# PWR_0V9_20A.net
KiCad netlist of a schematic drawn in Altium Designer
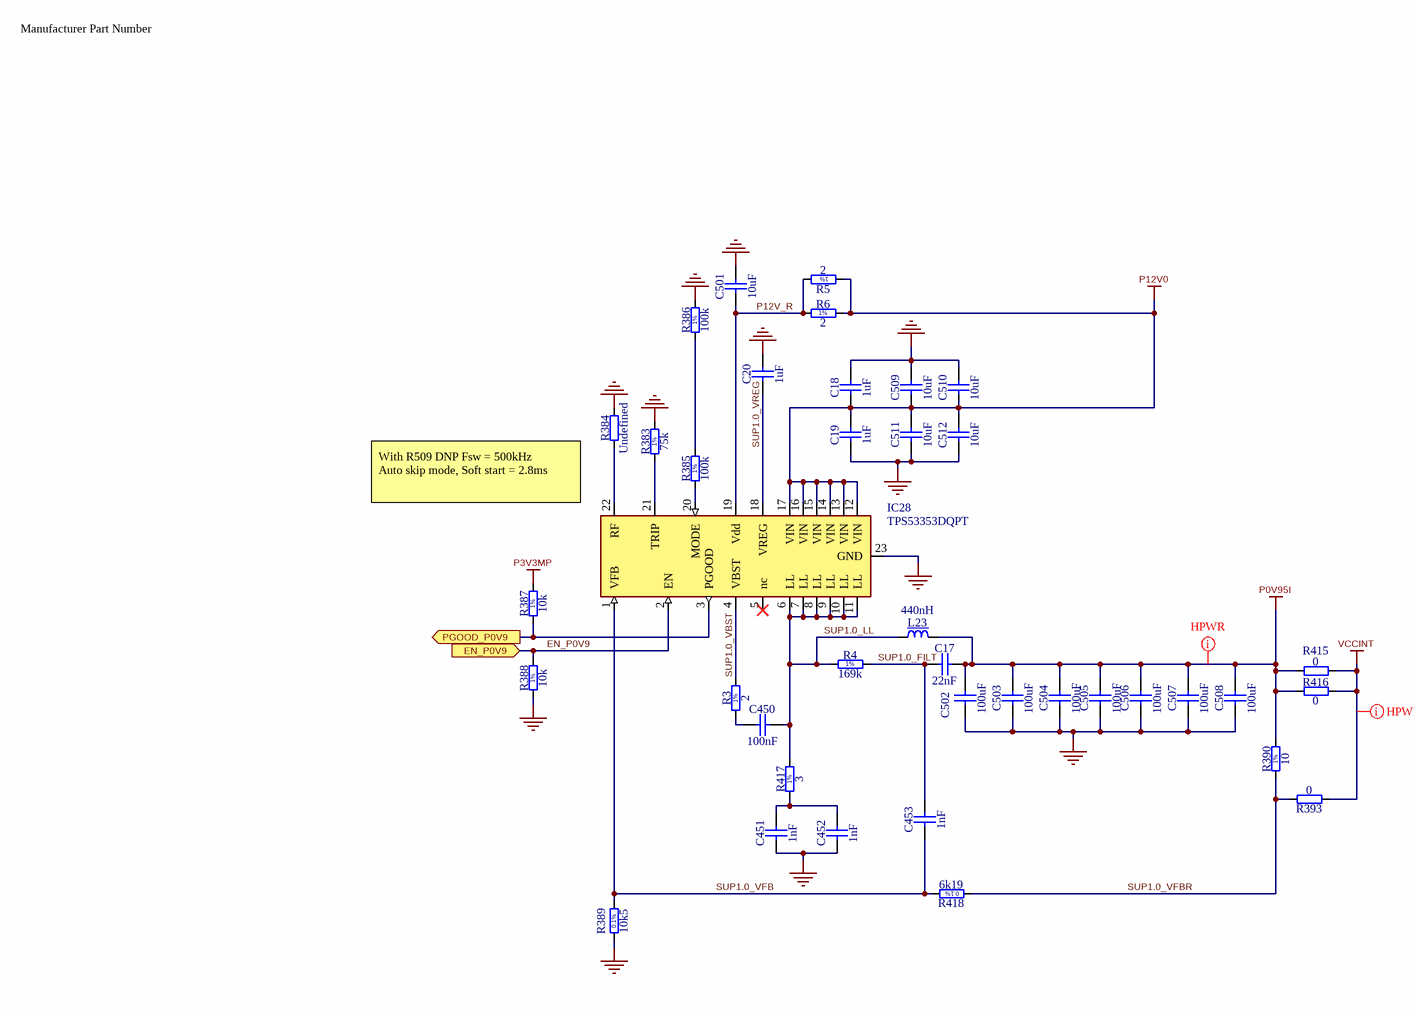
[diagram p0: PWR_0V9_20A.SchDoc]

(export (version "E")
  (design (tool "Eeschema 10.0.6"))
  (components
    (comp (ref "C17")
      (value "22nF")
      (footprint "CAPC1608X87N")
      (description "Non-polarised capacitor")
      (fields
        (field (name "MANUFACTURER PART NUMBER") "CC0603_22NF_50V_10%_X7R")
        (field (name "MANUFACTURER") "GENERIC")
        (field (name "AUTHOR") "CERN DEM JLC")
      )
      (libsource (lib "Capacitors") (part "Capacitor - non polarized"))
    )
    (comp (ref "C18")
      (value "1uF")
      (footprint "CAPC1608X87N")
      (description "Non-polarised capacitor")
      (fields
        (field (name "MANUFACTURER PART NUMBER") "CC0603_1UF_25V_10%_X7R")
        (field (name "MANUFACTURER") "GENERIC")
        (field (name "AUTHOR") "CERN DEM JLC")
      )
      (libsource (lib "Capacitors") (part "Capacitor - non polarized"))
    )
    (comp (ref "C19")
      (value "1uF")
      (footprint "CAPC1608X87N")
      (description "Non-polarised capacitor")
      (fields
        (field (name "MANUFACTURER PART NUMBER") "CC0603_1UF_25V_10%_X7R")
        (field (name "MANUFACTURER") "GENERIC")
        (field (name "AUTHOR") "CERN DEM JLC")
      )
      (libsource (lib "Capacitors") (part "Capacitor - non polarized"))
    )
    (comp (ref "C20")
      (value "1uF")
      (footprint "CAPC1608X87N")
      (description "Non-polarised capacitor")
      (fields
        (field (name "MANUFACTURER PART NUMBER") "CC0603_1UF_25V_10%_X7R")
        (field (name "MANUFACTURER") "GENERIC")
        (field (name "AUTHOR") "CERN DEM JLC")
      )
      (libsource (lib "Capacitors") (part "Capacitor - non polarized"))
    )
    (comp (ref "C450")
      (value "100nF")
      (footprint "CAPC1005X55N")
      (description "Non-polarised capacitor")
      (fields
        (field (name "MANUFACTURER PART NUMBER") "CC0402_100NF_16V_10%_X5R")
        (field (name "MANUFACTURER") "GENERIC")
        (field (name "AUTHOR") "CERN DEM JLC")
      )
      (libsource (lib "Capacitors") (part "Capacitor - non polarized"))
    )
    (comp (ref "C451")
      (value "1nF")
      (footprint "CAPC1005X55N")
      (description "Non-polarised capacitor")
      (fields
        (field (name "MANUFACTURER PART NUMBER") "CC0402_1NF_50V_10%_X7R")
        (field (name "MANUFACTURER") "GENERIC")
        (field (name "AUTHOR") "CERN DEM JLC")
      )
      (libsource (lib "Capacitors") (part "Capacitor - non polarized"))
    )
    (comp (ref "C452")
      (value "1nF")
      (footprint "CAPC1005X55N")
      (description "Non-polarised capacitor")
      (fields
        (field (name "MANUFACTURER PART NUMBER") "CC0402_1NF_50V_10%_X7R")
        (field (name "MANUFACTURER") "GENERIC")
        (field (name "AUTHOR") "CERN DEM JLC")
      )
      (libsource (lib "Capacitors") (part "Capacitor - non polarized"))
    )
    (comp (ref "C453")
      (value "1nF")
      (footprint "CAPC1005X55N")
      (description "Non-polarised capacitor")
      (fields
        (field (name "MANUFACTURER PART NUMBER") "CC0402_1NF_50V_10%_X7R")
        (field (name "MANUFACTURER") "GENERIC")
        (field (name "AUTHOR") "CERN DEM JLC")
      )
      (libsource (lib "Capacitors") (part "Capacitor - non polarized"))
    )
    (comp (ref "C501")
      (value "10uF")
      (footprint "CAPC3216X180N")
      (description "Non-polarised capacitor")
      (fields
        (field (name "MANUFACTURER PART NUMBER") "CC1206_10uF_25V_10%_X7R")
        (field (name "MANUFACTURER") "GENERIC")
        (field (name "AUTHOR") "CERN DEM JLC")
      )
      (libsource (lib "Capacitors") (part "Capacitor - non polarized"))
    )
    (comp (ref "C502")
      (value "100uF")
      (footprint "CAPC3216X180N")
      (description "Non-polarised capacitor")
      (fields
        (field (name "MANUFACTURER PART NUMBER") "CC1206_100UF_6.3V_20%_X5R")
        (field (name "MANUFACTURER") "GENERIC")
        (field (name "AUTHOR") "CERN DEM JLC")
      )
      (libsource (lib "Capacitors") (part "Capacitor - non polarized"))
    )
    (comp (ref "C503")
      (value "100uF")
      (footprint "CAPC3216X180N")
      (description "Non-polarised capacitor")
      (fields
        (field (name "MANUFACTURER PART NUMBER") "CC1206_100UF_6.3V_20%_X5R")
        (field (name "MANUFACTURER") "GENERIC")
        (field (name "AUTHOR") "CERN DEM JLC")
      )
      (libsource (lib "Capacitors") (part "Capacitor - non polarized"))
    )
    (comp (ref "C504")
      (value "100uF")
      (footprint "CAPC3216X180N")
      (description "Non-polarised capacitor")
      (fields
        (field (name "MANUFACTURER PART NUMBER") "CC1206_100UF_6.3V_20%_X5R")
        (field (name "MANUFACTURER") "GENERIC")
        (field (name "AUTHOR") "CERN DEM JLC")
      )
      (libsource (lib "Capacitors") (part "Capacitor - non polarized"))
    )
    (comp (ref "C505")
      (value "100uF")
      (footprint "CAPC3216X180N")
      (description "Non-polarised capacitor")
      (fields
        (field (name "MANUFACTURER PART NUMBER") "CC1206_100UF_6.3V_20%_X5R")
        (field (name "MANUFACTURER") "GENERIC")
        (field (name "AUTHOR") "CERN DEM JLC")
      )
      (libsource (lib "Capacitors") (part "Capacitor - non polarized"))
    )
    (comp (ref "C506")
      (value "100uF")
      (footprint "CAPC3216X180N")
      (description "Non-polarised capacitor")
      (fields
        (field (name "MANUFACTURER PART NUMBER") "CC1206_100UF_6.3V_20%_X5R")
        (field (name "MANUFACTURER") "GENERIC")
        (field (name "AUTHOR") "CERN DEM JLC")
      )
      (libsource (lib "Capacitors") (part "Capacitor - non polarized"))
    )
    (comp (ref "C507")
      (value "100uF")
      (footprint "CAPC3216X180N")
      (description "Non-polarised capacitor")
      (fields
        (field (name "MANUFACTURER PART NUMBER") "CC1206_100UF_6.3V_20%_X5R")
        (field (name "MANUFACTURER") "GENERIC")
        (field (name "AUTHOR") "CERN DEM JLC")
      )
      (libsource (lib "Capacitors") (part "Capacitor - non polarized"))
    )
    (comp (ref "C508")
      (value "100uF")
      (footprint "CAPC3216X180N")
      (description "Non-polarised capacitor")
      (fields
        (field (name "MANUFACTURER PART NUMBER") "CC1206_100UF_6.3V_20%_X5R")
        (field (name "MANUFACTURER") "GENERIC")
        (field (name "AUTHOR") "CERN DEM JLC")
      )
      (libsource (lib "Capacitors") (part "Capacitor - non polarized"))
    )
    (comp (ref "C509")
      (value "10uF")
      (footprint "CAPC3216X180N")
      (description "Non-polarised capacitor")
      (fields
        (field (name "MANUFACTURER PART NUMBER") "CC1206_10uF_25V_10%_X7R")
        (field (name "MANUFACTURER") "GENERIC")
        (field (name "AUTHOR") "CERN DEM JLC")
      )
      (libsource (lib "Capacitors") (part "Capacitor - non polarized"))
    )
    (comp (ref "C510")
      (value "10uF")
      (footprint "CAPC3216X180N")
      (description "Non-polarised capacitor")
      (fields
        (field (name "MANUFACTURER PART NUMBER") "CC1206_10uF_25V_10%_X7R")
        (field (name "MANUFACTURER") "GENERIC")
        (field (name "AUTHOR") "CERN DEM JLC")
      )
      (libsource (lib "Capacitors") (part "Capacitor - non polarized"))
    )
    (comp (ref "C511")
      (value "10uF")
      (footprint "CAPC3216X180N")
      (description "Non-polarised capacitor")
      (fields
        (field (name "MANUFACTURER PART NUMBER") "CC1206_10uF_25V_10%_X7R")
        (field (name "MANUFACTURER") "GENERIC")
        (field (name "AUTHOR") "CERN DEM JLC")
      )
      (libsource (lib "Capacitors") (part "Capacitor - non polarized"))
    )
    (comp (ref "C512")
      (value "10uF")
      (footprint "CAPC3216X180N")
      (description "Non-polarised capacitor")
      (fields
        (field (name "MANUFACTURER PART NUMBER") "CC1206_10uF_25V_10%_X7R")
        (field (name "MANUFACTURER") "GENERIC")
        (field (name "AUTHOR") "CERN DEM JLC")
      )
      (libsource (lib "Capacitors") (part "Capacitor - non polarized"))
    )
    (comp (ref "IC28")
      (value "TPS53353DQPT")
      (footprint "LCCS50P600X500X150-22N")
      (description "High-Efficiency 20-A Synchronous Buck Converter with Eco-mode™")
      (libsource (lib "LIBRARY_SCH") (part "PM_TPS53353"))
    )
    (comp (ref "L23")
      (value "440nH")
      (footprint "IND_PULSE_PA0513")
      (description "Inductor With Core")
      (fields
        (field (name "MANUFACTURER PART NUMBER") "PA0513.441NLT")
        (field (name "MANUFACTURER") "PULSE ELECTRONICS")
        (field (name "AUTHOR") "CERN DEM JLC")
      )
      (libsource (lib "Inductors & Transformers") (part "Inductor With Magnetic core"))
    )
    (comp (ref "R3")
      (value "2")
      (footprint "RESC1608X55N")
      (description "Resistor - 1%")
      (fields
        (field (name "MANUFACTURER PART NUMBER") "R0603_2R_1%_0.1W_200PPM")
        (field (name "MANUFACTURER") "GENERIC")
        (field (name "AUTHOR") "CERN DEM JLC")
      )
      (libsource (lib "Resistors") (part "Resistor - 1%"))
    )
    (comp (ref "R4")
      (value "169k")
      (footprint "RESC1608X55N")
      (description "Resistor - 1%")
      (fields
        (field (name "MANUFACTURER PART NUMBER") "R0603_169K_1%_0.1W_100PPM")
        (field (name "MANUFACTURER") "GENERIC")
        (field (name "AUTHOR") "CERN DEM JLC")
      )
      (libsource (lib "Resistors") (part "Resistor - 1%"))
    )
    (comp (ref "R5")
      (value "2")
      (footprint "RESC1608X55N")
      (description "Resistor - 1%")
      (fields
        (field (name "MANUFACTURER PART NUMBER") "R0603_2R_1%_0.1W_200PPM")
        (field (name "MANUFACTURER") "GENERIC")
        (field (name "AUTHOR") "CERN DEM JLC")
      )
      (libsource (lib "Resistors") (part "Resistor - 1%"))
    )
    (comp (ref "R6")
      (value "2")
      (footprint "RESC1608X55N")
      (description "Resistor - 1%")
      (fields
        (field (name "MANUFACTURER PART NUMBER") "R0603_2R_1%_0.1W_200PPM")
        (field (name "MANUFACTURER") "GENERIC")
        (field (name "AUTHOR") "CERN DEM JLC")
      )
      (libsource (lib "Resistors") (part "Resistor - 1%"))
    )
    (comp (ref "R383")
      (value "75k")
      (footprint "RESC1005X40N")
      (description "Resistor - 1%")
      (fields
        (field (name "MANUFACTURER PART NUMBER") "R0402_75K_1%_0.0625W_100PPM")
        (field (name "MANUFACTURER") "GENERIC")
        (field (name "AUTHOR") "CERN DEM JLC")
      )
      (libsource (lib "Resistors") (part "Resistor - 1%"))
    )
    (comp (ref "R384")
      (value "Undefined")
      (footprint "RESC1005X40N")
      (description "Resistor")
      (fields
        (field (name "MANUFACTURER PART NUMBER") "R0402_NO-VALUE")
        (field (name "AUTHOR") "CERN DEM JLC")
      )
      (libsource (lib "Resistors") (part "Resistor"))
    )
    (comp (ref "R385")
      (value "100k")
      (footprint "RESC1005X40N")
      (description "Resistor - 1%")
      (fields
        (field (name "MANUFACTURER PART NUMBER") "R0402_100K_1%_0.0625W_100PPM")
        (field (name "MANUFACTURER") "GENERIC")
        (field (name "AUTHOR") "CERN DEM JLC")
      )
      (libsource (lib "Resistors") (part "Resistor - 1%"))
    )
    (comp (ref "R386")
      (value "100k")
      (footprint "RESC1005X40N")
      (description "Resistor - 1%")
      (fields
        (field (name "MANUFACTURER PART NUMBER") "R0402_100K_1%_0.0625W_100PPM")
        (field (name "MANUFACTURER") "GENERIC")
        (field (name "AUTHOR") "CERN DEM JLC")
      )
      (libsource (lib "Resistors") (part "Resistor - 1%"))
    )
    (comp (ref "R387")
      (value "10k")
      (footprint "RESC1005X40N")
      (description "Resistor - 1%")
      (fields
        (field (name "MANUFACTURER PART NUMBER") "R0402_10K_1%_0.0625W_100PPM")
        (field (name "MANUFACTURER") "GENERIC")
        (field (name "AUTHOR") "CERN DEM JLC")
      )
      (libsource (lib "Resistors") (part "Resistor - 1%"))
    )
    (comp (ref "R388")
      (value "10k")
      (footprint "RESC1005X40N")
      (description "Resistor - 1%")
      (fields
        (field (name "MANUFACTURER PART NUMBER") "R0402_10K_1%_0.0625W_100PPM")
        (field (name "MANUFACTURER") "GENERIC")
        (field (name "AUTHOR") "CERN DEM JLC")
      )
      (libsource (lib "Resistors") (part "Resistor - 1%"))
    )
    (comp (ref "R389")
      (value "10k5")
      (footprint "RESC1608X55N")
      (description "Resistor - 0.1%")
      (fields
        (field (name "MANUFACTURER PART NUMBER") "R0603_10K5_0.1%_0.063W_10PPM")
        (field (name "MANUFACTURER") "GENERIC")
        (field (name "AUTHOR") "CERN DEM JLC")
      )
      (libsource (lib "Resistors") (part "Resistor - 0.1%"))
    )
    (comp (ref "R390")
      (value "10")
      (footprint "RESC1005X40N")
      (description "Resistor - 1%")
      (fields
        (field (name "MANUFACTURER PART NUMBER") "R0402_10R_1%_0.0625W_200PPM")
        (field (name "MANUFACTURER") "GENERIC")
        (field (name "AUTHOR") "CERN DEM JLC")
      )
      (libsource (lib "Resistors") (part "Resistor - 1%"))
    )
    (comp (ref "R393")
      (value "0")
      (footprint "RESC1005X40N")
      (description "Resistor")
      (fields
        (field (name "MANUFACTURER PART NUMBER") "R0402_0R_JUMPER")
        (field (name "MANUFACTURER") "GENERIC")
        (field (name "AUTHOR") "CERN DEM JLC")
      )
      (libsource (lib "Resistors") (part "Resistor"))
    )
    (comp (ref "R415")
      (value "0")
      (footprint "RESC6331X70N")
      (description "Resistor")
      (fields
        (field (name "MANUFACTURER PART NUMBER") "R2512_0R_JUMPER")
        (field (name "MANUFACTURER") "GENERIC")
        (field (name "AUTHOR") "CERN DEM JLC")
      )
      (libsource (lib "Resistors") (part "Resistor"))
    )
    (comp (ref "R416")
      (value "0")
      (footprint "RESC6331X70N")
      (description "Resistor")
      (fields
        (field (name "MANUFACTURER PART NUMBER") "R2512_0R_JUMPER")
        (field (name "MANUFACTURER") "GENERIC")
        (field (name "AUTHOR") "CERN DEM JLC")
      )
      (libsource (lib "Resistors") (part "Resistor"))
    )
    (comp (ref "R417")
      (value "3")
      (footprint "RESC3216X65N")
      (description "Resistor - 1%")
      (fields
        (field (name "MANUFACTURER PART NUMBER") "R1206_3R_1%_0.25W_200PPM")
        (field (name "MANUFACTURER") "GENERIC")
        (field (name "AUTHOR") "CERN DEM JLC")
      )
      (libsource (lib "Resistors") (part "Resistor - 1%"))
    )
    (comp (ref "R418")
      (value "6k19")
      (footprint "RESC1608X55N")
      (description "Resistor - 0.1%")
      (fields
        (field (name "MANUFACTURER PART NUMBER") "R0603_6K19_0.1%_0.063W_10PPM")
        (field (name "MANUFACTURER") "GENERIC")
        (field (name "AUTHOR") "CERN DEM JLC")
      )
      (libsource (lib "Resistors") (part "Resistor - 0.1%"))
    )
  )
  (nets
    (net (code "1") (name "/EN_P0V9") (class "Default")
      (node (ref "IC28") (pin "2") (pinfunction "EN_2") (pintype "input"))
      (node (ref "R388") (pin "2") (pinfunction "2_2") (pintype "passive"))
    )
    (net (code "2") (name "/P12V_R") (class "Default")
      (node (ref "C501") (pin "1") (pinfunction "1_1") (pintype "passive"))
      (node (ref "IC28") (pin "19") (pinfunction "Vdd_19") (pintype "power_in"))
      (node (ref "R5") (pin "1") (pinfunction "1_1") (pintype "passive"))
      (node (ref "R6") (pin "1") (pinfunction "1_1") (pintype "passive"))
    )
    (net (code "3") (name "/PGOOD_P0V9") (class "Default")
      (node (ref "IC28") (pin "3") (pinfunction "PGOOD_3") (pintype "output"))
      (node (ref "R387") (pin "1") (pinfunction "1_1") (pintype "passive"))
    )
    (net (code "4") (name "/SUP1.0_FILT") (class "Default")
      (node (ref "C17") (pin "1") (pinfunction "1_1") (pintype "passive"))
      (node (ref "C453") (pin "2") (pinfunction "2_2") (pintype "passive"))
      (node (ref "R4") (pin "2") (pinfunction "2_2") (pintype "passive"))
    )
    (net (code "5") (name "/SUP1.0_LL") (class "Default")
      (node (ref "C450") (pin "2") (pinfunction "2_2") (pintype "passive"))
      (node (ref "IC28") (pin "10") (pinfunction "LL_10") (pintype "passive"))
      (node (ref "IC28") (pin "11") (pinfunction "LL_11") (pintype "passive"))
      (node (ref "IC28") (pin "6") (pinfunction "LL_6") (pintype "passive"))
      (node (ref "IC28") (pin "7") (pinfunction "LL_7") (pintype "passive"))
      (node (ref "IC28") (pin "8") (pinfunction "LL_8") (pintype "passive"))
      (node (ref "IC28") (pin "9") (pinfunction "LL_9") (pintype "passive"))
      (node (ref "L23") (pin "1") (pinfunction "1_1") (pintype "passive"))
      (node (ref "R4") (pin "1") (pinfunction "1_1") (pintype "passive"))
      (node (ref "R417") (pin "2") (pinfunction "2_2") (pintype "passive"))
    )
    (net (code "6") (name "/SUP1.0_VBST") (class "Default")
      (node (ref "IC28") (pin "4") (pinfunction "VBST_4") (pintype "passive"))
      (node (ref "R3") (pin "2") (pinfunction "2_2") (pintype "passive"))
    )
    (net (code "7") (name "/SUP1.0_VFB") (class "Default")
      (node (ref "C453") (pin "1") (pinfunction "1_1") (pintype "passive"))
      (node (ref "IC28") (pin "1") (pinfunction "VFB_1") (pintype "input"))
      (node (ref "R389") (pin "2") (pinfunction "2_2") (pintype "passive"))
      (node (ref "R418") (pin "2") (pinfunction "2_2") (pintype "passive"))
    )
    (net (code "8") (name "/SUP1.0_VFBR") (class "Default")
      (node (ref "R390") (pin "1") (pinfunction "1_1") (pintype "passive"))
      (node (ref "R393") (pin "2") (pinfunction "2_2") (pintype "passive"))
      (node (ref "R418") (pin "1") (pinfunction "1_1") (pintype "passive"))
    )
    (net (code "9") (name "/SUP1.0_VREG") (class "Default")
      (node (ref "C20") (pin "1") (pinfunction "1_1") (pintype "passive"))
      (node (ref "IC28") (pin "18") (pinfunction "VREG_18") (pintype "power_in"))
    )
    (net (code "10") (name "GND") (class "Default")
      (node (ref "C18") (pin "2") (pinfunction "2_2") (pintype "passive"))
      (node (ref "C19") (pin "1") (pinfunction "1_1") (pintype "passive"))
      (node (ref "C20") (pin "2") (pinfunction "2_2") (pintype "passive"))
      (node (ref "C451") (pin "1") (pinfunction "1_1") (pintype "passive"))
      (node (ref "C452") (pin "1") (pinfunction "1_1") (pintype "passive"))
      (node (ref "C501") (pin "2") (pinfunction "2_2") (pintype "passive"))
      (node (ref "C502") (pin "1") (pinfunction "1_1") (pintype "passive"))
      (node (ref "C503") (pin "1") (pinfunction "1_1") (pintype "passive"))
      (node (ref "C504") (pin "1") (pinfunction "1_1") (pintype "passive"))
      (node (ref "C505") (pin "1") (pinfunction "1_1") (pintype "passive"))
      (node (ref "C506") (pin "1") (pinfunction "1_1") (pintype "passive"))
      (node (ref "C507") (pin "1") (pinfunction "1_1") (pintype "passive"))
      (node (ref "C508") (pin "1") (pinfunction "1_1") (pintype "passive"))
      (node (ref "C509") (pin "2") (pinfunction "2_2") (pintype "passive"))
      (node (ref "C510") (pin "2") (pinfunction "2_2") (pintype "passive"))
      (node (ref "C511") (pin "1") (pinfunction "1_1") (pintype "passive"))
      (node (ref "C512") (pin "1") (pinfunction "1_1") (pintype "passive"))
      (node (ref "IC28") (pin "23") (pinfunction "GND_23") (pintype "power_in"))
      (node (ref "R383") (pin "2") (pinfunction "2_2") (pintype "passive"))
      (node (ref "R384") (pin "2") (pinfunction "2_2") (pintype "passive"))
      (node (ref "R386") (pin "2") (pinfunction "2_2") (pintype "passive"))
      (node (ref "R388") (pin "1") (pinfunction "1_1") (pintype "passive"))
      (node (ref "R389") (pin "1") (pinfunction "1_1") (pintype "passive"))
    )
    (net (code "11") (name "Net-(C450-Pad1)") (class "Default")
      (node (ref "C450") (pin "1") (pinfunction "1_1") (pintype "passive"))
      (node (ref "R3") (pin "1") (pinfunction "1_1") (pintype "passive"))
    )
    (net (code "12") (name "Net-(C451-Pad2)") (class "Default")
      (node (ref "C451") (pin "2") (pinfunction "2_2") (pintype "passive"))
      (node (ref "C452") (pin "2") (pinfunction "2_2") (pintype "passive"))
      (node (ref "R417") (pin "1") (pinfunction "1_1") (pintype "passive"))
    )
    (net (code "13") (name "Net-(IC28-MODE)") (class "Default")
      (node (ref "IC28") (pin "20") (pinfunction "MODE_20") (pintype "input"))
      (node (ref "R385") (pin "1") (pinfunction "1_1") (pintype "passive"))
    )
    (net (code "14") (name "Net-(IC28-RF)") (class "Default")
      (node (ref "IC28") (pin "22") (pinfunction "RF_22") (pintype "passive"))
      (node (ref "R384") (pin "1") (pinfunction "1_1") (pintype "passive"))
    )
    (net (code "15") (name "Net-(IC28-TRIP)") (class "Default")
      (node (ref "IC28") (pin "21") (pinfunction "TRIP_21") (pintype "passive"))
      (node (ref "R383") (pin "1") (pinfunction "1_1") (pintype "passive"))
    )
    (net (code "16") (name "Net-(R385-Pad2)") (class "Default")
      (node (ref "R385") (pin "2") (pinfunction "2_2") (pintype "passive"))
      (node (ref "R386") (pin "1") (pinfunction "1_1") (pintype "passive"))
    )
    (net (code "17") (name "P0V95I") (class "Default")
      (node (ref "C17") (pin "2") (pinfunction "2_2") (pintype "passive"))
      (node (ref "C502") (pin "2") (pinfunction "2_2") (pintype "passive"))
      (node (ref "C503") (pin "2") (pinfunction "2_2") (pintype "passive"))
      (node (ref "C504") (pin "2") (pinfunction "2_2") (pintype "passive"))
      (node (ref "C505") (pin "2") (pinfunction "2_2") (pintype "passive"))
      (node (ref "C506") (pin "2") (pinfunction "2_2") (pintype "passive"))
      (node (ref "C507") (pin "2") (pinfunction "2_2") (pintype "passive"))
      (node (ref "C508") (pin "2") (pinfunction "2_2") (pintype "passive"))
      (node (ref "L23") (pin "2") (pinfunction "2_2") (pintype "passive"))
      (node (ref "R390") (pin "2") (pinfunction "2_2") (pintype "passive"))
      (node (ref "R415") (pin "1") (pinfunction "1_1") (pintype "passive"))
      (node (ref "R416") (pin "1") (pinfunction "1_1") (pintype "passive"))
    )
    (net (code "18") (name "P3V3MP") (class "Default")
      (node (ref "R387") (pin "2") (pinfunction "2_2") (pintype "passive"))
    )
    (net (code "19") (name "P12V0") (class "Default")
      (node (ref "C18") (pin "1") (pinfunction "1_1") (pintype "passive"))
      (node (ref "C19") (pin "2") (pinfunction "2_2") (pintype "passive"))
      (node (ref "C509") (pin "1") (pinfunction "1_1") (pintype "passive"))
      (node (ref "C510") (pin "1") (pinfunction "1_1") (pintype "passive"))
      (node (ref "C511") (pin "2") (pinfunction "2_2") (pintype "passive"))
      (node (ref "C512") (pin "2") (pinfunction "2_2") (pintype "passive"))
      (node (ref "IC28") (pin "12") (pinfunction "VIN_12") (pintype "power_in"))
      (node (ref "IC28") (pin "13") (pinfunction "VIN_13") (pintype "power_in"))
      (node (ref "IC28") (pin "14") (pinfunction "VIN_14") (pintype "power_in"))
      (node (ref "IC28") (pin "15") (pinfunction "VIN_15") (pintype "power_in"))
      (node (ref "IC28") (pin "16") (pinfunction "VIN_16") (pintype "power_in"))
      (node (ref "IC28") (pin "17") (pinfunction "VIN_17") (pintype "power_in"))
      (node (ref "R5") (pin "2") (pinfunction "2_2") (pintype "passive"))
      (node (ref "R6") (pin "2") (pinfunction "2_2") (pintype "passive"))
    )
    (net (code "20") (name "VCCINT") (class "Default")
      (node (ref "R393") (pin "1") (pinfunction "1_1") (pintype "passive"))
      (node (ref "R415") (pin "2") (pinfunction "2_2") (pintype "passive"))
      (node (ref "R416") (pin "2") (pinfunction "2_2") (pintype "passive"))
    )
    (net (code "21") (name "unconnected-(IC28-nc-Pad5)") (class "Default")
      (node (ref "IC28") (pin "5") (pinfunction "nc_5") (pintype "passive+no_connect"))
    )
  )
)
